# M3_Discrete_Interface.net
KiCad netlist of a schematic drawn in Altium Designer
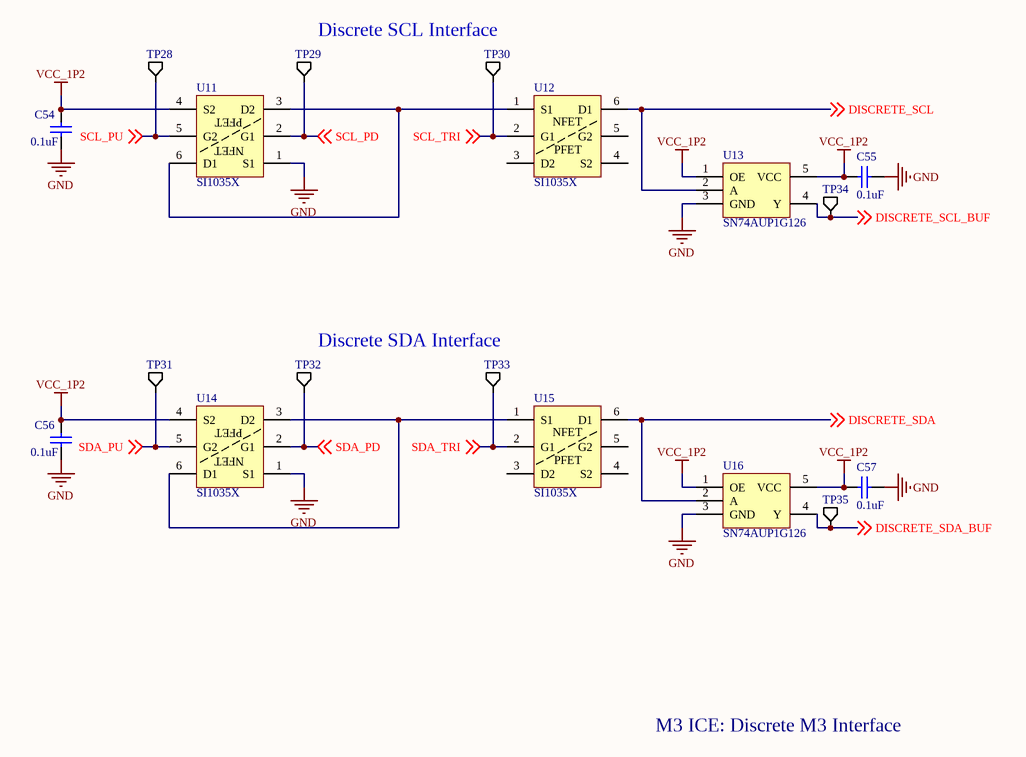
[diagram p0: M3_Discrete_Interface.SchDoc]

(export (version "E")
  (design (tool "Eeschema 10.0.6"))
  (components
    (comp (ref "C54")
      (value "0.1uF")
      (footprint "1608[0603]")
      (description "Capacitor (Semiconductor SIM Model)")
      (fields
        (field (name "DISTPARTNO") "445-1317-1-ND")
        (field (name "MANPARTNO") "C1608X7R1C104K")
        (field (name "PUBLISHER") "Altium Limited")
      )
      (libsource (lib "Miscellaneous Devices") (part "Cap Semi"))
    )
    (comp (ref "C55")
      (value "0.1uF")
      (footprint "1608[0603]")
      (description "Capacitor (Semiconductor SIM Model)")
      (fields
        (field (name "DISTPARTNO") "445-1317-1-ND")
        (field (name "MANPARTNO") "C1608X7R1C104K")
        (field (name "PUBLISHER") "Altium Limited")
      )
      (libsource (lib "Miscellaneous Devices") (part "Cap Semi"))
    )
    (comp (ref "C56")
      (value "0.1uF")
      (footprint "1608[0603]")
      (description "Capacitor (Semiconductor SIM Model)")
      (fields
        (field (name "DISTPARTNO") "445-1317-1-ND")
        (field (name "MANPARTNO") "C1608X7R1C104K")
        (field (name "PUBLISHER") "Altium Limited")
      )
      (libsource (lib "Miscellaneous Devices") (part "Cap Semi"))
    )
    (comp (ref "C57")
      (value "0.1uF")
      (footprint "1608[0603]")
      (description "Capacitor (Semiconductor SIM Model)")
      (fields
        (field (name "DISTPARTNO") "445-1317-1-ND")
        (field (name "MANPARTNO") "C1608X7R1C104K")
        (field (name "PUBLISHER") "Altium Limited")
      )
      (libsource (lib "Miscellaneous Devices") (part "Cap Semi"))
    )
    (comp (ref "TP28") (value "TP") (footprint "TP") (libsource (lib "M3") (part "TP")))
    (comp (ref "TP29") (value "TP") (footprint "TP") (libsource (lib "M3") (part "TP")))
    (comp (ref "TP30") (value "TP") (footprint "TP") (libsource (lib "M3") (part "TP")))
    (comp (ref "TP31") (value "TP") (footprint "TP") (libsource (lib "M3") (part "TP")))
    (comp (ref "TP32") (value "TP") (footprint "TP") (libsource (lib "M3") (part "TP")))
    (comp (ref "TP33") (value "TP") (footprint "TP") (libsource (lib "M3") (part "TP")))
    (comp (ref "TP34") (value "TP") (footprint "TP") (libsource (lib "M3") (part "TP")))
    (comp (ref "TP35") (value "TP") (footprint "TP") (libsource (lib "M3") (part "TP")))
    (comp (ref "U11")
      (value "SI1035X")
      (footprint "SC-89-6")
      (description "Complementary N- and P-Channel 20 V (D-S) MOSFET")
      (fields (field (name "DISTPARTNO") "SI1035X-T1-GE3CT-ND") (field (name "MANPARTNO") "SI1035X-T1-GE3"))
      (libsource (lib "M3") (part "SI1035X"))
    )
    (comp (ref "U12")
      (value "SI1035X")
      (footprint "SC-89-6")
      (description "Complementary N- and P-Channel 20 V (D-S) MOSFET")
      (fields (field (name "DISTPARTNO") "SI1035X-T1-GE3CT-ND") (field (name "MANPARTNO") "SI1035X-T1-GE3"))
      (libsource (lib "") (part "SI1035X_1"))
    )
    (comp (ref "U13")
      (value "SN74AUP1G126")
      (footprint "SOT-753")
      (description "LOW-POWER SINGLE BUS BUFFER GATE WITH 3-STATE OUTPUT")
      (fields (field (name "DISTPARTNO") "296-18005-1-ND") (field (name "MANPARTNO") "SN74AUP1G126DBVR"))
      (libsource (lib "M3") (part "SN74AUP1G126"))
    )
    (comp (ref "U14")
      (value "SI1035X")
      (footprint "SC-89-6")
      (description "Complementary N- and P-Channel 20 V (D-S) MOSFET")
      (fields (field (name "DISTPARTNO") "SI1035X-T1-GE3CT-ND") (field (name "MANPARTNO") "SI1035X-T1-GE3"))
      (libsource (lib "M3") (part "SI1035X"))
    )
    (comp (ref "U15")
      (value "SI1035X")
      (footprint "SC-89-6")
      (description "Complementary N- and P-Channel 20 V (D-S) MOSFET")
      (fields (field (name "DISTPARTNO") "SI1035X-T1-GE3CT-ND") (field (name "MANPARTNO") "SI1035X-T1-GE3"))
      (libsource (lib "") (part "SI1035X_1"))
    )
    (comp (ref "U16")
      (value "SN74AUP1G126")
      (footprint "SOT-753")
      (description "LOW-POWER SINGLE BUS BUFFER GATE WITH 3-STATE OUTPUT")
      (fields (field (name "DISTPARTNO") "296-18005-1-ND") (field (name "MANPARTNO") "SN74AUP1G126DBVR"))
      (libsource (lib "M3") (part "SN74AUP1G126"))
    )
  )
  (nets
    (net (code "1") (name "DISCRETE_SCL") (class "Default")
      (node (ref "U12") (pin "6") (pinfunction "D1_6") (pintype "passive"))
      (node (ref "U13") (pin "2") (pinfunction "A_2") (pintype "passive"))
    )
    (net (code "2") (name "DISCRETE_SCL_BUF") (class "Default")
      (node (ref "TP34") (pin "1") (pinfunction "A_1") (pintype "passive"))
      (node (ref "U13") (pin "4") (pinfunction "Y_4") (pintype "passive"))
    )
    (net (code "3") (name "DISCRETE_SDA") (class "Default")
      (node (ref "U15") (pin "6") (pinfunction "D1_6") (pintype "passive"))
      (node (ref "U16") (pin "2") (pinfunction "A_2") (pintype "passive"))
    )
    (net (code "4") (name "DISCRETE_SDA_BUF") (class "Default")
      (node (ref "TP35") (pin "1") (pinfunction "A_1") (pintype "passive"))
      (node (ref "U16") (pin "4") (pinfunction "Y_4") (pintype "passive"))
    )
    (net (code "5") (name "GND") (class "Default")
      (node (ref "C54") (pin "1") (pinfunction "1_1") (pintype "passive"))
      (node (ref "C55") (pin "1") (pinfunction "1_1") (pintype "passive"))
      (node (ref "C56") (pin "1") (pinfunction "1_1") (pintype "passive"))
      (node (ref "C57") (pin "1") (pinfunction "1_1") (pintype "passive"))
      (node (ref "U11") (pin "1") (pinfunction "S1_1") (pintype "passive"))
      (node (ref "U13") (pin "3") (pinfunction "GND_3") (pintype "passive"))
      (node (ref "U14") (pin "1") (pinfunction "S1_1") (pintype "passive"))
      (node (ref "U16") (pin "3") (pinfunction "GND_3") (pintype "passive"))
    )
    (net (code "6") (name "Net-(U11-D1)") (class "Default")
      (node (ref "U11") (pin "3") (pinfunction "D2_3") (pintype "passive"))
      (node (ref "U11") (pin "6") (pinfunction "D1_6") (pintype "passive"))
      (node (ref "U12") (pin "1") (pinfunction "S1_1") (pintype "passive"))
    )
    (net (code "7") (name "Net-(U14-D1)") (class "Default")
      (node (ref "U14") (pin "3") (pinfunction "D2_3") (pintype "passive"))
      (node (ref "U14") (pin "6") (pinfunction "D1_6") (pintype "passive"))
      (node (ref "U15") (pin "1") (pinfunction "S1_1") (pintype "passive"))
    )
    (net (code "8") (name "SCL_PD") (class "Default")
      (node (ref "TP29") (pin "1") (pinfunction "A_1") (pintype "passive"))
      (node (ref "U11") (pin "2") (pinfunction "G1_2") (pintype "passive"))
    )
    (net (code "9") (name "SCL_PU") (class "Default")
      (node (ref "TP28") (pin "1") (pinfunction "A_1") (pintype "passive"))
      (node (ref "U11") (pin "5") (pinfunction "G2_5") (pintype "passive"))
    )
    (net (code "10") (name "SCL_TRI") (class "Default")
      (node (ref "TP30") (pin "1") (pinfunction "A_1") (pintype "passive"))
      (node (ref "U12") (pin "2") (pinfunction "G1_2") (pintype "passive"))
    )
    (net (code "11") (name "SDA_PD") (class "Default")
      (node (ref "TP32") (pin "1") (pinfunction "A_1") (pintype "passive"))
      (node (ref "U14") (pin "2") (pinfunction "G1_2") (pintype "passive"))
    )
    (net (code "12") (name "SDA_PU") (class "Default")
      (node (ref "TP31") (pin "1") (pinfunction "A_1") (pintype "passive"))
      (node (ref "U14") (pin "5") (pinfunction "G2_5") (pintype "passive"))
    )
    (net (code "13") (name "SDA_TRI") (class "Default")
      (node (ref "TP33") (pin "1") (pinfunction "A_1") (pintype "passive"))
      (node (ref "U15") (pin "2") (pinfunction "G1_2") (pintype "passive"))
    )
    (net (code "14") (name "VCC_1P2") (class "Default")
      (node (ref "C54") (pin "2") (pinfunction "2_2") (pintype "passive"))
      (node (ref "C55") (pin "2") (pinfunction "2_2") (pintype "passive"))
      (node (ref "C56") (pin "2") (pinfunction "2_2") (pintype "passive"))
      (node (ref "C57") (pin "2") (pinfunction "2_2") (pintype "passive"))
      (node (ref "U11") (pin "4") (pinfunction "S2_4") (pintype "passive"))
      (node (ref "U13") (pin "1") (pinfunction "OE_1") (pintype "passive"))
      (node (ref "U13") (pin "5") (pinfunction "VCC_5") (pintype "passive"))
      (node (ref "U14") (pin "4") (pinfunction "S2_4") (pintype "passive"))
      (node (ref "U16") (pin "1") (pinfunction "OE_1") (pintype "passive"))
      (node (ref "U16") (pin "5") (pinfunction "VCC_5") (pintype "passive"))
    )
    (net (code "15") (name "unconnected-(U12-D2-Pad3)") (class "Default")
      (node (ref "U12") (pin "3") (pinfunction "D2_3") (pintype "passive"))
    )
    (net (code "16") (name "unconnected-(U12-G2-Pad5)") (class "Default")
      (node (ref "U12") (pin "5") (pinfunction "G2_5") (pintype "passive"))
    )
    (net (code "17") (name "unconnected-(U12-S2-Pad4)") (class "Default")
      (node (ref "U12") (pin "4") (pinfunction "S2_4") (pintype "passive"))
    )
    (net (code "18") (name "unconnected-(U15-D2-Pad3)") (class "Default")
      (node (ref "U15") (pin "3") (pinfunction "D2_3") (pintype "passive"))
    )
    (net (code "19") (name "unconnected-(U15-G2-Pad5)") (class "Default")
      (node (ref "U15") (pin "5") (pinfunction "G2_5") (pintype "passive"))
    )
    (net (code "20") (name "unconnected-(U15-S2-Pad4)") (class "Default")
      (node (ref "U15") (pin "4") (pinfunction "S2_4") (pintype "passive"))
    )
  )
)
